# FdbkCtrl_v01.net
KiCad netlist of a schematic drawn in EAGLE
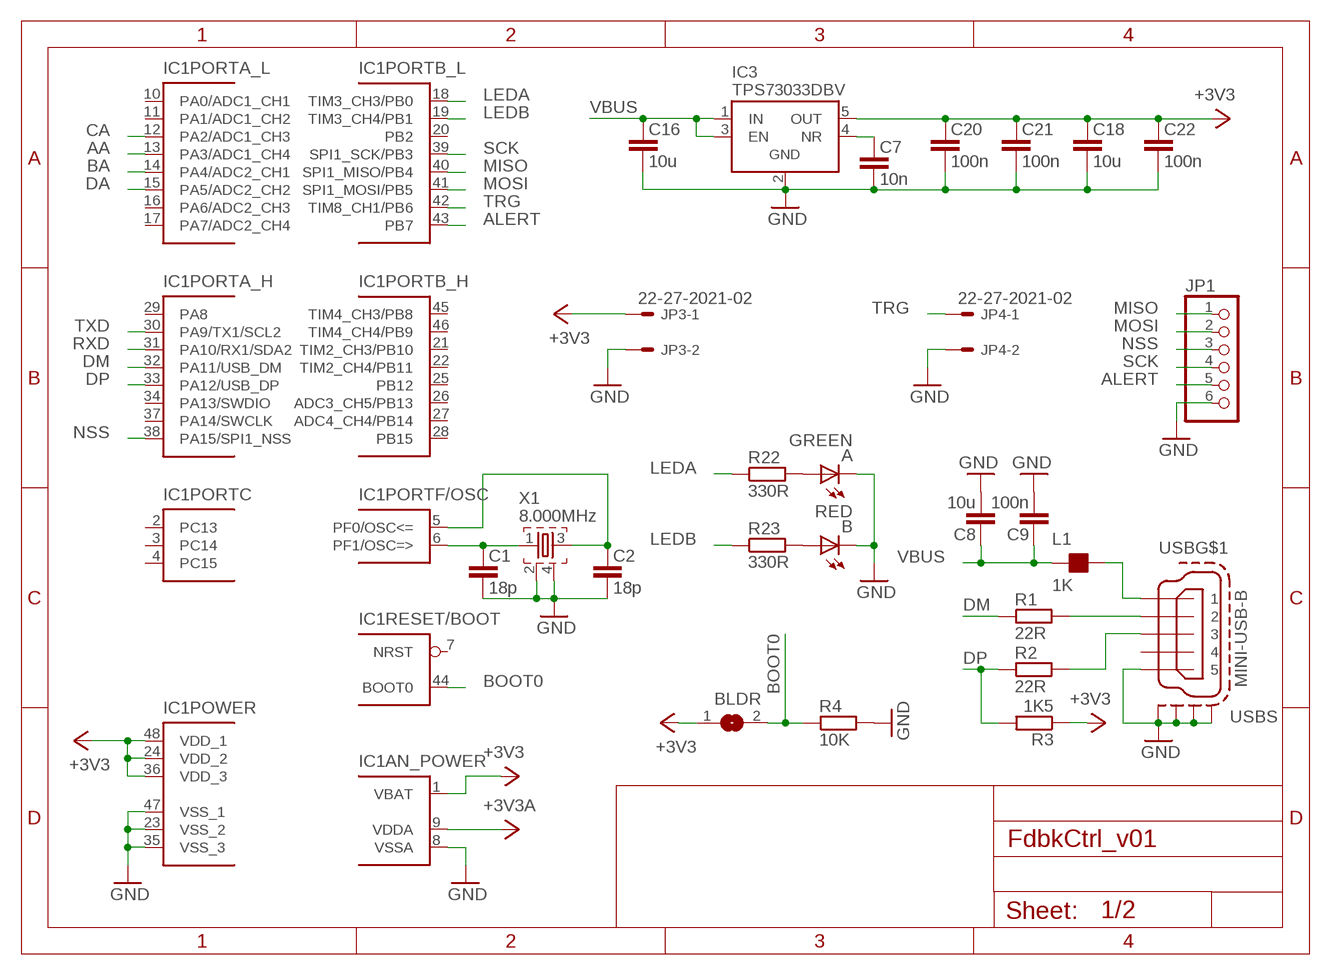
[diagram p0: schematic, sheet 1]
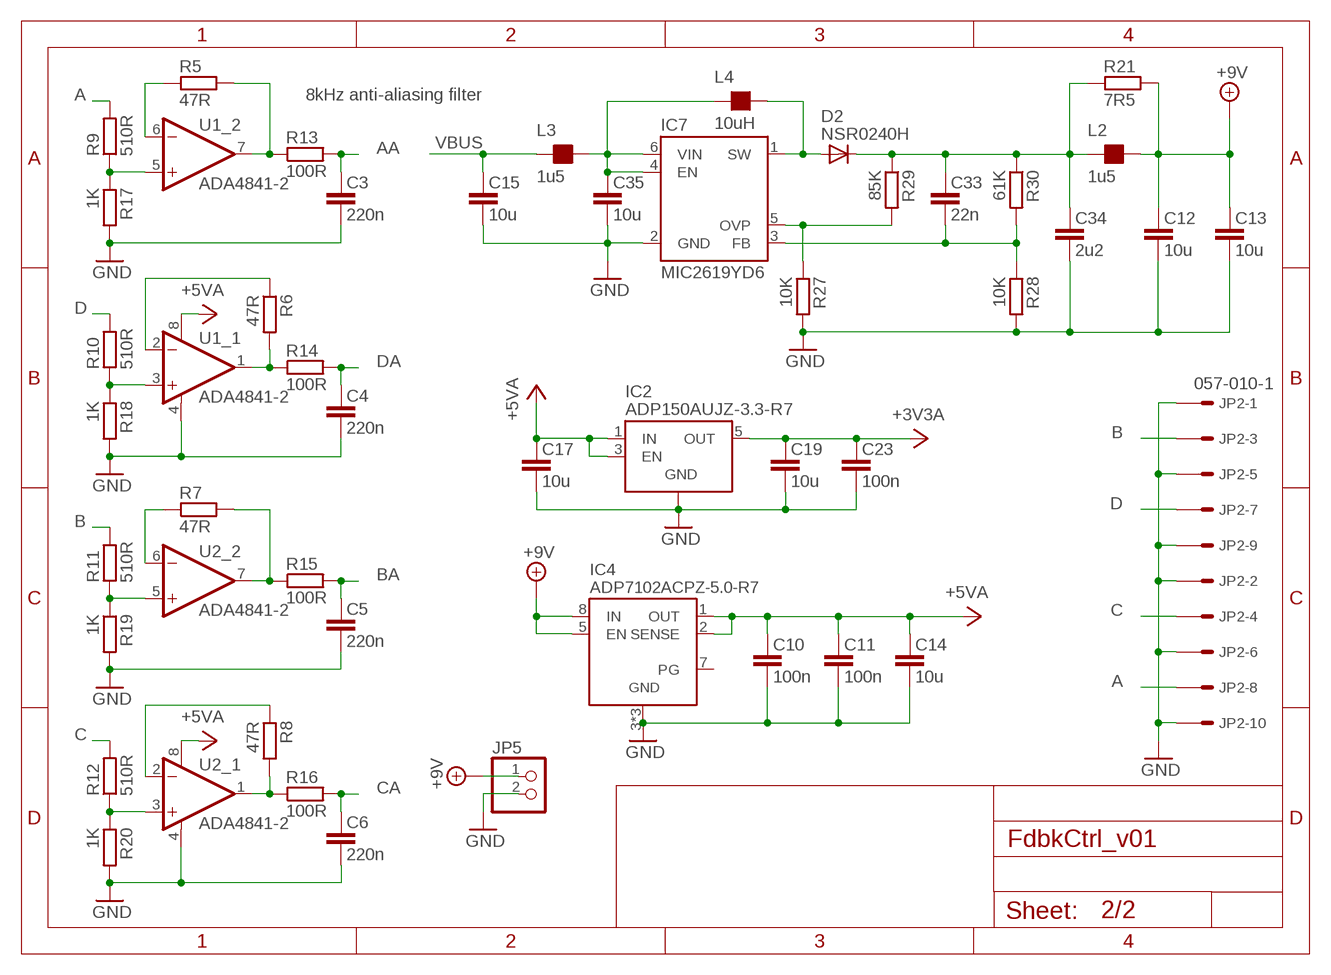
[diagram p1: schematic, sheet 2]

(export (version "E")
  (design (tool "Eeschema 10.0.6"))
  (components
    (comp (ref "C3")
      (value "220n")
      (footprint "eagle-import:C0603G")
      (libsource (lib "eagle-import") (part "C_EU_C0603G"))
    )
    (comp (ref "C4")
      (value "220n")
      (footprint "eagle-import:C0603G")
      (libsource (lib "eagle-import") (part "C_EU_C0603G"))
    )
    (comp (ref "C5")
      (value "220n")
      (footprint "eagle-import:C0603G")
      (libsource (lib "eagle-import") (part "C_EU_C0603G"))
    )
    (comp (ref "C6")
      (value "220n")
      (footprint "eagle-import:C0603G")
      (libsource (lib "eagle-import") (part "C_EU_C0603G"))
    )
    (comp (ref "C10")
      (value "100n")
      (footprint "eagle-import:C0603G")
      (libsource (lib "eagle-import") (part "C_EU_C0603G"))
    )
    (comp (ref "C11")
      (value "100n")
      (footprint "eagle-import:C0603G")
      (libsource (lib "eagle-import") (part "C_EU_C0603G"))
    )
    (comp (ref "C12")
      (value "10u")
      (footprint "eagle-import:C0805G")
      (libsource (lib "eagle-import") (part "C_EU_C0805G"))
    )
    (comp (ref "C13")
      (value "10u")
      (footprint "eagle-import:C0805G")
      (libsource (lib "eagle-import") (part "C_EU_C0805G"))
    )
    (comp (ref "C14")
      (value "10u")
      (footprint "eagle-import:C0805G")
      (libsource (lib "eagle-import") (part "C_EU_C0805G"))
    )
    (comp (ref "C15")
      (value "10u")
      (footprint "eagle-import:C0805G")
      (libsource (lib "eagle-import") (part "C_EU_C0805G"))
    )
    (comp (ref "C17")
      (value "10u")
      (footprint "eagle-import:C0805G")
      (libsource (lib "eagle-import") (part "C_EU_C0805G"))
    )
    (comp (ref "C19")
      (value "10u")
      (footprint "eagle-import:C0805G")
      (libsource (lib "eagle-import") (part "C_EU_C0805G"))
    )
    (comp (ref "C23")
      (value "100n")
      (footprint "eagle-import:C0402G")
      (libsource (lib "eagle-import") (part "C_EU_C0402G"))
    )
    (comp (ref "C33")
      (value "22n")
      (footprint "eagle-import:C0603")
      (libsource (lib "eagle-import") (part "C_EU_C0603"))
    )
    (comp (ref "C34")
      (value "2u2")
      (footprint "eagle-import:C0805G")
      (libsource (lib "eagle-import") (part "C_EU_C0805G"))
    )
    (comp (ref "C35")
      (value "10u")
      (footprint "eagle-import:C0805G")
      (libsource (lib "eagle-import") (part "C_EU_C0805G"))
    )
    (comp (ref "D2")
      (value "NSR0240H")
      (footprint "eagle-import:SOD323")
      (libsource (lib "eagle-import") (part "NSR0240H"))
    )
    (comp (ref "IC2")
      (value "ADP150AUJZ-3.3-R7")
      (footprint "eagle-import:SOT23-5")
      (libsource (lib "eagle-import") (part "ADP150AUJZ-3.3-R7"))
    )
    (comp (ref "IC4")
      (value "ADP7102ACPZ-5.0-R7")
      (footprint "eagle-import:LFCSP8")
      (libsource (lib "eagle-import") (part "ADP7102ACPZ-5.0-R7"))
    )
    (comp (ref "IC7")
      (value "MIC2619YD6")
      (footprint "eagle-import:SOT23-6")
      (libsource (lib "eagle-import") (part "MIC2619YD6"))
    )
    (comp (ref "JP2")
      (value "057-010-1")
      (footprint "eagle-import:057-010-1")
      (libsource (lib "eagle-import") (part "057-010-1"))
    )
    (comp (ref "JP5")
      (value "PINHD-1X2")
      (footprint "eagle-import:1X02")
      (libsource (lib "eagle-import") (part "PINHD-1X2"))
    )
    (comp (ref "L2")
      (value "1u5")
      (footprint "eagle-import:L2010")
      (libsource (lib "eagle-import") (part "FB_2010"))
    )
    (comp (ref "L3")
      (value "1u5")
      (footprint "eagle-import:L2010")
      (libsource (lib "eagle-import") (part "FB_2010"))
    )
    (comp (ref "L4")
      (value "10uH")
      (footprint "eagle-import:L1210")
      (libsource (lib "eagle-import") (part "FB_1210"))
    )
    (comp (ref "R5")
      (value "47R")
      (footprint "eagle-import:R0603")
      (libsource (lib "eagle-import") (part "R_EU_R0603"))
    )
    (comp (ref "R6")
      (value "47R")
      (footprint "eagle-import:R0603")
      (libsource (lib "eagle-import") (part "R_EU_R0603"))
    )
    (comp (ref "R7")
      (value "47R")
      (footprint "eagle-import:R0603")
      (libsource (lib "eagle-import") (part "R_EU_R0603"))
    )
    (comp (ref "R8")
      (value "47R")
      (footprint "eagle-import:R0603")
      (libsource (lib "eagle-import") (part "R_EU_R0603"))
    )
    (comp (ref "R9")
      (value "510R")
      (footprint "eagle-import:R0603")
      (libsource (lib "eagle-import") (part "R_EU_R0603"))
    )
    (comp (ref "R10")
      (value "510R")
      (footprint "eagle-import:R0603")
      (libsource (lib "eagle-import") (part "R_EU_R0603"))
    )
    (comp (ref "R11")
      (value "510R")
      (footprint "eagle-import:R0603")
      (libsource (lib "eagle-import") (part "R_EU_R0603"))
    )
    (comp (ref "R12")
      (value "510R")
      (footprint "eagle-import:R0603")
      (libsource (lib "eagle-import") (part "R_EU_R0603"))
    )
    (comp (ref "R13")
      (value "100R")
      (footprint "eagle-import:R0603")
      (libsource (lib "eagle-import") (part "R_EU_R0603"))
    )
    (comp (ref "R14")
      (value "100R")
      (footprint "eagle-import:R0603")
      (libsource (lib "eagle-import") (part "R_EU_R0603"))
    )
    (comp (ref "R15")
      (value "100R")
      (footprint "eagle-import:R0603")
      (libsource (lib "eagle-import") (part "R_EU_R0603"))
    )
    (comp (ref "R16")
      (value "100R")
      (footprint "eagle-import:R0603")
      (libsource (lib "eagle-import") (part "R_EU_R0603"))
    )
    (comp (ref "R17")
      (value "1K")
      (footprint "eagle-import:R0603G")
      (libsource (lib "eagle-import") (part "R_EU_R0603G"))
    )
    (comp (ref "R18")
      (value "1K")
      (footprint "eagle-import:R0603G")
      (libsource (lib "eagle-import") (part "R_EU_R0603G"))
    )
    (comp (ref "R19")
      (value "1K")
      (footprint "eagle-import:R0603G")
      (libsource (lib "eagle-import") (part "R_EU_R0603G"))
    )
    (comp (ref "R20")
      (value "1K")
      (footprint "eagle-import:R0603G")
      (libsource (lib "eagle-import") (part "R_EU_R0603G"))
    )
    (comp (ref "R21")
      (value "7R5")
      (footprint "eagle-import:R0805")
      (libsource (lib "eagle-import") (part "R_EU_R0805"))
    )
    (comp (ref "R27")
      (value "10K")
      (footprint "eagle-import:R0603G")
      (libsource (lib "eagle-import") (part "R_EU_R0603G"))
    )
    (comp (ref "R28")
      (value "10K")
      (footprint "eagle-import:R0603G")
      (libsource (lib "eagle-import") (part "R_EU_R0603G"))
    )
    (comp (ref "R29")
      (value "85K")
      (footprint "eagle-import:R0603")
      (libsource (lib "eagle-import") (part "R_EU_R0603"))
    )
    (comp (ref "R30")
      (value "61K")
      (footprint "eagle-import:R0603")
      (libsource (lib "eagle-import") (part "R_EU_R0603"))
    )
    (comp (ref "U1")
      (value "ADA4841-2")
      (footprint "eagle-import:SOIC-8")
      (libsource (lib "eagle-import") (part "ADA4841-2"))
    )
    (comp (ref "U2")
      (value "ADA4841-2")
      (footprint "eagle-import:SOIC-8")
      (libsource (lib "eagle-import") (part "ADA4841-2"))
    )
    (comp (ref "A")
      (value "GREEN")
      (footprint "eagle-import:CHIPLED_0805")
      (libsource (lib "eagle-import") (part "LEDCHIPLED_0805"))
    )
    (comp (ref "B")
      (value "RED")
      (footprint "eagle-import:CHIPLED_0805")
      (libsource (lib "eagle-import") (part "LEDCHIPLED_0805"))
    )
    (comp (ref "BLDR")
      (value "SJ")
      (footprint "eagle-import:SJ")
      (libsource (lib "eagle-import") (part "SJ"))
    )
    (comp (ref "C1")
      (value "18p")
      (footprint "eagle-import:C0603G")
      (libsource (lib "eagle-import") (part "C_EU_C0603G"))
    )
    (comp (ref "C2")
      (value "18p")
      (footprint "eagle-import:C0603G")
      (libsource (lib "eagle-import") (part "C_EU_C0603G"))
    )
    (comp (ref "C7")
      (value "10n")
      (footprint "eagle-import:C0402G")
      (libsource (lib "eagle-import") (part "C_EU_C0402G"))
    )
    (comp (ref "C8")
      (value "10u")
      (footprint "eagle-import:C0805G")
      (libsource (lib "eagle-import") (part "C_EU_C0805G"))
    )
    (comp (ref "C9")
      (value "100n")
      (footprint "eagle-import:C0603G")
      (libsource (lib "eagle-import") (part "C_EU_C0603G"))
    )
    (comp (ref "C16")
      (value "10u")
      (footprint "eagle-import:C0805G")
      (libsource (lib "eagle-import") (part "C_EU_C0805G"))
    )
    (comp (ref "C18")
      (value "10u")
      (footprint "eagle-import:C0805G")
      (libsource (lib "eagle-import") (part "C_EU_C0805G"))
    )
    (comp (ref "C20")
      (value "100n")
      (footprint "eagle-import:C0402G")
      (libsource (lib "eagle-import") (part "C_EU_C0402G"))
    )
    (comp (ref "C21")
      (value "100n")
      (footprint "eagle-import:C0402G")
      (libsource (lib "eagle-import") (part "C_EU_C0402G"))
    )
    (comp (ref "C22")
      (value "100n")
      (footprint "eagle-import:C0402G")
      (libsource (lib "eagle-import") (part "C_EU_C0402G"))
    )
    (comp (ref "IC1")
      (value "STM32F303CXT6")
      (footprint "eagle-import:LQFP48")
      (libsource (lib "eagle-import") (part "STM32F303CXT6"))
    )
    (comp (ref "IC3")
      (value "TPS73033DBV")
      (footprint "eagle-import:SOT23-5")
      (libsource (lib "eagle-import") (part "TPS73033DBV"))
    )
    (comp (ref "JP1")
      (value "PINHD-1X6")
      (footprint "eagle-import:1X06")
      (libsource (lib "eagle-import") (part "PINHD-1X6"))
    )
    (comp (ref "JP3")
      (value "22-27-2021-02")
      (footprint "eagle-import:6410-02")
      (libsource (lib "eagle-import") (part "22-?-0227-2021"))
    )
    (comp (ref "JP4")
      (value "22-27-2021-02")
      (footprint "eagle-import:6410-02")
      (libsource (lib "eagle-import") (part "22-?-0227-2021"))
    )
    (comp (ref "L1")
      (value "1K")
      (footprint "eagle-import:L0603")
      (libsource (lib "eagle-import") (part "FB_0603"))
    )
    (comp (ref "R1")
      (value "22R")
      (footprint "eagle-import:R0603")
      (libsource (lib "eagle-import") (part "R_EU_R0603"))
    )
    (comp (ref "R2")
      (value "22R")
      (footprint "eagle-import:R0603")
      (libsource (lib "eagle-import") (part "R_EU_R0603"))
    )
    (comp (ref "R3")
      (value "1K5")
      (footprint "eagle-import:R0603")
      (libsource (lib "eagle-import") (part "R_EU_R0603"))
    )
    (comp (ref "R4")
      (value "10K")
      (footprint "eagle-import:R0603G")
      (libsource (lib "eagle-import") (part "R_EU_R0603G"))
    )
    (comp (ref "R22")
      (value "330R")
      (footprint "eagle-import:R0603")
      (libsource (lib "eagle-import") (part "R_EU_R0603"))
    )
    (comp (ref "R23")
      (value "330R")
      (footprint "eagle-import:R0603")
      (libsource (lib "eagle-import") (part "R_EU_R0603"))
    )
    (comp (ref "USB")
      (value "MINI-USB-B")
      (footprint "eagle-import:32005-201")
      (libsource (lib "eagle-import") (part "MINI-USB-SCHIELD-32005-201"))
    )
    (comp (ref "X1")
      (value "8.000MHz")
      (footprint "eagle-import:ABMM2")
      (libsource (lib "eagle-import") (part "ABMM2"))
    )
  )
  (nets
    (net (code "1") (name "+3V3") (class "Default")
      (node (ref "BLDR") (pin "1") (pinfunction "1_1") (pintype "passive"))
      (node (ref "C18") (pin "1") (pinfunction "1_1") (pintype "passive"))
      (node (ref "C20") (pin "1") (pinfunction "1_1") (pintype "passive"))
      (node (ref "C21") (pin "1") (pinfunction "1_1") (pintype "passive"))
      (node (ref "C22") (pin "1") (pinfunction "1_1") (pintype "passive"))
      (node (ref "IC1") (pin "1") (pinfunction "VBAT_1") (pintype "power_in"))
      (node (ref "IC1") (pin "24") (pinfunction "VDD_2_24") (pintype "power_in"))
      (node (ref "IC1") (pin "36") (pinfunction "VDD_3_36") (pintype "power_in"))
      (node (ref "IC1") (pin "48") (pinfunction "VDD_1_48") (pintype "power_in"))
      (node (ref "IC3") (pin "5") (pinfunction "OUT_5") (pintype "power_in"))
      (node (ref "JP3") (pin "1") (pinfunction "S_1") (pintype "passive"))
      (node (ref "R3") (pin "1") (pinfunction "1_1") (pintype "passive"))
    )
    (net (code "2") (name "+3V3A") (class "Default")
      (node (ref "C19") (pin "1") (pinfunction "1_1") (pintype "passive"))
      (node (ref "C23") (pin "1") (pinfunction "1_1") (pintype "passive"))
      (node (ref "IC1") (pin "9") (pinfunction "VDDA_9") (pintype "power_in"))
      (node (ref "IC2") (pin "5") (pinfunction "OUT_5") (pintype "power_in"))
    )
    (net (code "3") (name "+5VA") (class "Default")
      (node (ref "C10") (pin "1") (pinfunction "1_1") (pintype "passive"))
      (node (ref "C11") (pin "1") (pinfunction "1_1") (pintype "passive"))
      (node (ref "C14") (pin "1") (pinfunction "1_1") (pintype "passive"))
      (node (ref "C17") (pin "1") (pinfunction "1_1") (pintype "passive"))
      (node (ref "IC2") (pin "1") (pinfunction "IN_1") (pintype "power_in"))
      (node (ref "IC2") (pin "3") (pinfunction "EN_3") (pintype "input"))
      (node (ref "IC4") (pin "1") (pinfunction "OUT_1") (pintype "power_in"))
      (node (ref "IC4") (pin "2") (pinfunction "SENSE_2") (pintype "input"))
      (node (ref "U1") (pin "8") (pinfunction "V+_8") (pintype "power_in"))
      (node (ref "U2") (pin "8") (pinfunction "V+_8") (pintype "power_in"))
    )
    (net (code "4") (name "+9V") (class "Default")
      (node (ref "C12") (pin "1") (pinfunction "1_1") (pintype "passive"))
      (node (ref "C13") (pin "1") (pinfunction "1_1") (pintype "passive"))
      (node (ref "IC4") (pin "5") (pinfunction "EN_5") (pintype "input"))
      (node (ref "IC4") (pin "8") (pinfunction "IN_8") (pintype "power_in"))
      (node (ref "JP5") (pin "1") (pinfunction "1_1") (pintype "passive"))
      (node (ref "L2") (pin "2") (pinfunction "2_2") (pintype "passive"))
      (node (ref "R21") (pin "2") (pinfunction "2_2") (pintype "passive"))
    )
    (net (code "5") (name "A") (class "Default")
      (node (ref "JP2") (pin "8") (pinfunction "S_8") (pintype "passive"))
      (node (ref "R9") (pin "2") (pinfunction "2_2") (pintype "passive"))
    )
    (net (code "6") (name "AA") (class "Default")
      (node (ref "C3") (pin "1") (pinfunction "1_1") (pintype "passive"))
      (node (ref "IC1") (pin "13") (pinfunction "PA3/ADC1_CH4_13") (pintype "bidirectional"))
      (node (ref "R13") (pin "2") (pinfunction "2_2") (pintype "passive"))
    )
    (net (code "7") (name "ALERT") (class "Default")
      (node (ref "IC1") (pin "43") (pinfunction "PB7_43") (pintype "bidirectional"))
      (node (ref "JP1") (pin "5") (pinfunction "5_5") (pintype "passive"))
    )
    (net (code "8") (name "B") (class "Default")
      (node (ref "JP2") (pin "3") (pinfunction "S_3") (pintype "passive"))
      (node (ref "R11") (pin "2") (pinfunction "2_2") (pintype "passive"))
    )
    (net (code "9") (name "BA") (class "Default")
      (node (ref "C5") (pin "1") (pinfunction "1_1") (pintype "passive"))
      (node (ref "IC1") (pin "14") (pinfunction "PA4/ADC2_CH1_14") (pintype "bidirectional"))
      (node (ref "R15") (pin "2") (pinfunction "2_2") (pintype "passive"))
    )
    (net (code "10") (name "BOOT0") (class "Default")
      (node (ref "BLDR") (pin "2") (pinfunction "2_2") (pintype "passive"))
      (node (ref "IC1") (pin "44") (pinfunction "BOOT0_44") (pintype "input"))
      (node (ref "R4") (pin "1") (pinfunction "1_1") (pintype "passive"))
    )
    (net (code "11") (name "C") (class "Default")
      (node (ref "JP2") (pin "4") (pinfunction "S_4") (pintype "passive"))
      (node (ref "R12") (pin "2") (pinfunction "2_2") (pintype "passive"))
    )
    (net (code "12") (name "CA") (class "Default")
      (node (ref "C6") (pin "1") (pinfunction "1_1") (pintype "passive"))
      (node (ref "IC1") (pin "12") (pinfunction "PA2/ADC1_CH3_12") (pintype "bidirectional"))
      (node (ref "R16") (pin "2") (pinfunction "2_2") (pintype "passive"))
    )
    (net (code "13") (name "D") (class "Default")
      (node (ref "JP2") (pin "7") (pinfunction "S_7") (pintype "passive"))
      (node (ref "R10") (pin "2") (pinfunction "2_2") (pintype "passive"))
    )
    (net (code "14") (name "DA") (class "Default")
      (node (ref "C4") (pin "1") (pinfunction "1_1") (pintype "passive"))
      (node (ref "IC1") (pin "15") (pinfunction "PA5/ADC2_CH2_15") (pintype "bidirectional"))
      (node (ref "R14") (pin "2") (pinfunction "2_2") (pintype "passive"))
    )
    (net (code "15") (name "DM") (class "Default")
      (node (ref "IC1") (pin "32") (pinfunction "PA11/USB_DM_32") (pintype "bidirectional"))
      (node (ref "R1") (pin "1") (pinfunction "1_1") (pintype "passive"))
    )
    (net (code "16") (name "DP") (class "Default")
      (node (ref "IC1") (pin "33") (pinfunction "PA12/USB_DP_33") (pintype "bidirectional"))
      (node (ref "R2") (pin "1") (pinfunction "1_1") (pintype "passive"))
      (node (ref "R3") (pin "2") (pinfunction "2_2") (pintype "passive"))
    )
    (net (code "17") (name "GND") (class "Default")
      (node (ref "A") (pin "C") (pinfunction "C_C") (pintype "passive"))
      (node (ref "B") (pin "C") (pinfunction "C_C") (pintype "passive"))
      (node (ref "C1") (pin "2") (pinfunction "2_2") (pintype "passive"))
      (node (ref "C10") (pin "2") (pinfunction "2_2") (pintype "passive"))
      (node (ref "C11") (pin "2") (pinfunction "2_2") (pintype "passive"))
      (node (ref "C12") (pin "2") (pinfunction "2_2") (pintype "passive"))
      (node (ref "C13") (pin "2") (pinfunction "2_2") (pintype "passive"))
      (node (ref "C14") (pin "2") (pinfunction "2_2") (pintype "passive"))
      (node (ref "C15") (pin "2") (pinfunction "2_2") (pintype "passive"))
      (node (ref "C16") (pin "2") (pinfunction "2_2") (pintype "passive"))
      (node (ref "C17") (pin "2") (pinfunction "2_2") (pintype "passive"))
      (node (ref "C18") (pin "2") (pinfunction "2_2") (pintype "passive"))
      (node (ref "C19") (pin "2") (pinfunction "2_2") (pintype "passive"))
      (node (ref "C2") (pin "2") (pinfunction "2_2") (pintype "passive"))
      (node (ref "C20") (pin "2") (pinfunction "2_2") (pintype "passive"))
      (node (ref "C21") (pin "2") (pinfunction "2_2") (pintype "passive"))
      (node (ref "C22") (pin "2") (pinfunction "2_2") (pintype "passive"))
      (node (ref "C23") (pin "2") (pinfunction "2_2") (pintype "passive"))
      (node (ref "C3") (pin "2") (pinfunction "2_2") (pintype "passive"))
      (node (ref "C34") (pin "2") (pinfunction "2_2") (pintype "passive"))
      (node (ref "C35") (pin "2") (pinfunction "2_2") (pintype "passive"))
      (node (ref "C4") (pin "2") (pinfunction "2_2") (pintype "passive"))
      (node (ref "C5") (pin "2") (pinfunction "2_2") (pintype "passive"))
      (node (ref "C6") (pin "2") (pinfunction "2_2") (pintype "passive"))
      (node (ref "C7") (pin "2") (pinfunction "2_2") (pintype "passive"))
      (node (ref "C8") (pin "2") (pinfunction "2_2") (pintype "passive"))
      (node (ref "C9") (pin "2") (pinfunction "2_2") (pintype "passive"))
      (node (ref "IC1") (pin "23") (pinfunction "VSS_2_23") (pintype "power_in"))
      (node (ref "IC1") (pin "35") (pinfunction "VSS_3_35") (pintype "power_in"))
      (node (ref "IC1") (pin "47") (pinfunction "VSS_1_47") (pintype "power_in"))
      (node (ref "IC1") (pin "8") (pinfunction "VSSA_8") (pintype "power_in"))
      (node (ref "IC2") (pin "2") (pinfunction "GND_2") (pintype "power_in"))
      (node (ref "IC3") (pin "2") (pinfunction "GND_2") (pintype "power_in"))
      (node (ref "IC4") (pin "3") (pinfunction "GND_3") (pintype "power_in"))
      (node (ref "IC4") (pin "6") (pinfunction "GND_6") (pintype "power_in"))
      (node (ref "IC4") (pin "EP") (pinfunction "GND_EP") (pintype "power_in"))
      (node (ref "IC7") (pin "2") (pinfunction "GND_2") (pintype "power_in"))
      (node (ref "JP1") (pin "6") (pinfunction "6_6") (pintype "passive"))
      (node (ref "JP2") (pin "1") (pinfunction "S_1") (pintype "passive"))
      (node (ref "JP2") (pin "10") (pinfunction "S_10") (pintype "passive"))
      (node (ref "JP2") (pin "2") (pinfunction "S_2") (pintype "passive"))
      (node (ref "JP2") (pin "5") (pinfunction "S_5") (pintype "passive"))
      (node (ref "JP2") (pin "6") (pinfunction "S_6") (pintype "passive"))
      (node (ref "JP2") (pin "9") (pinfunction "S_9") (pintype "passive"))
      (node (ref "JP3") (pin "2") (pinfunction "S_2") (pintype "passive"))
      (node (ref "JP4") (pin "2") (pinfunction "S_2") (pintype "passive"))
      (node (ref "JP5") (pin "2") (pinfunction "2_2") (pintype "passive"))
      (node (ref "R17") (pin "2") (pinfunction "2_2") (pintype "passive"))
      (node (ref "R18") (pin "2") (pinfunction "2_2") (pintype "passive"))
      (node (ref "R19") (pin "2") (pinfunction "2_2") (pintype "passive"))
      (node (ref "R20") (pin "2") (pinfunction "2_2") (pintype "passive"))
      (node (ref "R27") (pin "2") (pinfunction "2_2") (pintype "passive"))
      (node (ref "R28") (pin "2") (pinfunction "2_2") (pintype "passive"))
      (node (ref "R4") (pin "2") (pinfunction "2_2") (pintype "passive"))
      (node (ref "U1") (pin "4") (pinfunction "V-_4") (pintype "power_in"))
      (node (ref "U2") (pin "4") (pinfunction "V-_4") (pintype "power_in"))
      (node (ref "USB") (pin "5") (pinfunction "5_5") (pintype "passive"))
      (node (ref "USB") (pin "M1") (pinfunction "S1_M1") (pintype "passive"))
      (node (ref "USB") (pin "M2") (pinfunction "S2_M2") (pintype "passive"))
      (node (ref "USB") (pin "M3") (pinfunction "S3_M3") (pintype "passive"))
      (node (ref "USB") (pin "M4") (pinfunction "S4_M4") (pintype "passive"))
      (node (ref "X1") (pin "2") (pinfunction "2_2") (pintype "passive"))
      (node (ref "X1") (pin "4") (pinfunction "4_4") (pintype "passive"))
    )
    (net (code "18") (name "LEDA") (class "Default")
      (node (ref "IC1") (pin "18") (pinfunction "TIM3_CH3/PB0_18") (pintype "bidirectional"))
      (node (ref "R22") (pin "1") (pinfunction "1_1") (pintype "passive"))
    )
    (net (code "19") (name "LEDB") (class "Default")
      (node (ref "IC1") (pin "19") (pinfunction "TIM3_CH4/PB1_19") (pintype "bidirectional"))
      (node (ref "R23") (pin "1") (pinfunction "1_1") (pintype "passive"))
    )
    (net (code "20") (name "MISO") (class "Default")
      (node (ref "IC1") (pin "40") (pinfunction "SPI1_MISO/PB4_40") (pintype "bidirectional"))
      (node (ref "JP1") (pin "1") (pinfunction "1_1") (pintype "passive"))
    )
    (net (code "21") (name "MOSI") (class "Default")
      (node (ref "IC1") (pin "41") (pinfunction "SPI1_MOSI/PB5_41") (pintype "bidirectional"))
      (node (ref "JP1") (pin "2") (pinfunction "2_2") (pintype "passive"))
    )
    (net (code "22") (name "NSS") (class "Default")
      (node (ref "IC1") (pin "38") (pinfunction "PA15/SPI1_NSS_38") (pintype "bidirectional"))
      (node (ref "JP1") (pin "3") (pinfunction "3_3") (pintype "passive"))
    )
    (net (code "23") (name "Net-(A-PadA)") (class "Default")
      (node (ref "A") (pin "A") (pinfunction "A_A") (pintype "passive"))
      (node (ref "R22") (pin "2") (pinfunction "2_2") (pintype "passive"))
    )
    (net (code "24") (name "Net-(B-PadA)") (class "Default")
      (node (ref "B") (pin "A") (pinfunction "A_A") (pintype "passive"))
      (node (ref "R23") (pin "2") (pinfunction "2_2") (pintype "passive"))
    )
    (net (code "25") (name "Net-(C33-Pad1)") (class "Default")
      (node (ref "C33") (pin "1") (pinfunction "1_1") (pintype "passive"))
      (node (ref "C34") (pin "1") (pinfunction "1_1") (pintype "passive"))
      (node (ref "D2") (pin "C") (pinfunction "C_C") (pintype "passive"))
      (node (ref "L2") (pin "1") (pinfunction "1_1") (pintype "passive"))
      (node (ref "R21") (pin "1") (pinfunction "1_1") (pintype "passive"))
      (node (ref "R29") (pin "1") (pinfunction "1_1") (pintype "passive"))
      (node (ref "R30") (pin "1") (pinfunction "1_1") (pintype "passive"))
    )
    (net (code "26") (name "Net-(IC1G-PF0{slash}OSC<=)") (class "Default")
      (node (ref "C2") (pin "1") (pinfunction "1_1") (pintype "passive"))
      (node (ref "IC1") (pin "5") (pinfunction "PF0/OSC<=_5") (pintype "bidirectional"))
      (node (ref "X1") (pin "3") (pinfunction "3_3") (pintype "passive"))
    )
    (net (code "27") (name "Net-(IC1G-PF1{slash}OSC=>)") (class "Default")
      (node (ref "C1") (pin "1") (pinfunction "1_1") (pintype "passive"))
      (node (ref "IC1") (pin "6") (pinfunction "PF1/OSC=>_6") (pintype "bidirectional"))
      (node (ref "X1") (pin "1") (pinfunction "1_1") (pintype "passive"))
    )
    (net (code "28") (name "Net-(IC3-NR)") (class "Default")
      (node (ref "C7") (pin "1") (pinfunction "1_1") (pintype "passive"))
      (node (ref "IC3") (pin "4") (pinfunction "NR_4") (pintype "passive"))
    )
    (net (code "29") (name "Net-(IC7-EN)") (class "Default")
      (node (ref "C35") (pin "1") (pinfunction "1_1") (pintype "passive"))
      (node (ref "IC7") (pin "4") (pinfunction "EN_4") (pintype "input"))
      (node (ref "IC7") (pin "6") (pinfunction "VIN_6") (pintype "power_in"))
      (node (ref "L3") (pin "2") (pinfunction "2_2") (pintype "passive"))
      (node (ref "L4") (pin "1") (pinfunction "1_1") (pintype "passive"))
    )
    (net (code "30") (name "Net-(IC7-FB)") (class "Default")
      (node (ref "C33") (pin "2") (pinfunction "2_2") (pintype "passive"))
      (node (ref "IC7") (pin "3") (pinfunction "FB_3") (pintype "input"))
      (node (ref "R28") (pin "1") (pinfunction "1_1") (pintype "passive"))
      (node (ref "R30") (pin "2") (pinfunction "2_2") (pintype "passive"))
    )
    (net (code "31") (name "Net-(IC7-OVP)") (class "Default")
      (node (ref "IC7") (pin "5") (pinfunction "OVP_5") (pintype "input"))
      (node (ref "R27") (pin "1") (pinfunction "1_1") (pintype "passive"))
      (node (ref "R29") (pin "2") (pinfunction "2_2") (pintype "passive"))
    )
    (net (code "32") (name "Net-(IC7-SW)") (class "Default")
      (node (ref "D2") (pin "A") (pinfunction "A_A") (pintype "passive"))
      (node (ref "IC7") (pin "1") (pinfunction "SW_1") (pintype "input"))
      (node (ref "L4") (pin "2") (pinfunction "2_2") (pintype "passive"))
    )
    (net (code "33") (name "Net-(L1-Pad2)") (class "Default")
      (node (ref "L1") (pin "2") (pinfunction "2_2") (pintype "passive"))
      (node (ref "USB") (pin "1") (pinfunction "1_1") (pintype "passive"))
    )
    (net (code "34") (name "Net-(R1-Pad2)") (class "Default")
      (node (ref "R1") (pin "2") (pinfunction "2_2") (pintype "passive"))
      (node (ref "USB") (pin "2") (pinfunction "2_2") (pintype "passive"))
    )
    (net (code "35") (name "Net-(R2-Pad2)") (class "Default")
      (node (ref "R2") (pin "2") (pinfunction "2_2") (pintype "passive"))
      (node (ref "USB") (pin "3") (pinfunction "3_3") (pintype "passive"))
    )
    (net (code "36") (name "Net-(U1A-+IN)") (class "Default")
      (node (ref "R10") (pin "1") (pinfunction "1_1") (pintype "passive"))
      (node (ref "R18") (pin "1") (pinfunction "1_1") (pintype "passive"))
      (node (ref "U1") (pin "3") (pinfunction "+IN_3") (pintype "input"))
    )
    (net (code "37") (name "Net-(U1A--IN)") (class "Default")
      (node (ref "R6") (pin "1") (pinfunction "1_1") (pintype "passive"))
      (node (ref "U1") (pin "2") (pinfunction "-IN_2") (pintype "input"))
    )
    (net (code "38") (name "Net-(U1A-OUT)") (class "Default")
      (node (ref "R14") (pin "1") (pinfunction "1_1") (pintype "passive"))
      (node (ref "R6") (pin "2") (pinfunction "2_2") (pintype "passive"))
      (node (ref "U1") (pin "1") (pinfunction "OUT_1") (pintype "output"))
    )
    (net (code "39") (name "Net-(U1B-+IN)") (class "Default")
      (node (ref "R17") (pin "1") (pinfunction "1_1") (pintype "passive"))
      (node (ref "R9") (pin "1") (pinfunction "1_1") (pintype "passive"))
      (node (ref "U1") (pin "5") (pinfunction "+IN_5") (pintype "input"))
    )
    (net (code "40") (name "Net-(U1B--IN)") (class "Default")
      (node (ref "R5") (pin "1") (pinfunction "1_1") (pintype "passive"))
      (node (ref "U1") (pin "6") (pinfunction "-IN_6") (pintype "input"))
    )
    (net (code "41") (name "Net-(U1B-OUT)") (class "Default")
      (node (ref "R13") (pin "1") (pinfunction "1_1") (pintype "passive"))
      (node (ref "R5") (pin "2") (pinfunction "2_2") (pintype "passive"))
      (node (ref "U1") (pin "7") (pinfunction "OUT_7") (pintype "output"))
    )
    (net (code "42") (name "Net-(U2A-+IN)") (class "Default")
      (node (ref "R12") (pin "1") (pinfunction "1_1") (pintype "passive"))
      (node (ref "R20") (pin "1") (pinfunction "1_1") (pintype "passive"))
      (node (ref "U2") (pin "3") (pinfunction "+IN_3") (pintype "input"))
    )
    (net (code "43") (name "Net-(U2A--IN)") (class "Default")
      (node (ref "R8") (pin "1") (pinfunction "1_1") (pintype "passive"))
      (node (ref "U2") (pin "2") (pinfunction "-IN_2") (pintype "input"))
    )
    (net (code "44") (name "Net-(U2A-OUT)") (class "Default")
      (node (ref "R16") (pin "1") (pinfunction "1_1") (pintype "passive"))
      (node (ref "R8") (pin "2") (pinfunction "2_2") (pintype "passive"))
      (node (ref "U2") (pin "1") (pinfunction "OUT_1") (pintype "output"))
    )
    (net (code "45") (name "Net-(U2B-+IN)") (class "Default")
      (node (ref "R11") (pin "1") (pinfunction "1_1") (pintype "passive"))
      (node (ref "R19") (pin "1") (pinfunction "1_1") (pintype "passive"))
      (node (ref "U2") (pin "5") (pinfunction "+IN_5") (pintype "input"))
    )
    (net (code "46") (name "Net-(U2B--IN)") (class "Default")
      (node (ref "R7") (pin "1") (pinfunction "1_1") (pintype "passive"))
      (node (ref "U2") (pin "6") (pinfunction "-IN_6") (pintype "input"))
    )
    (net (code "47") (name "Net-(U2B-OUT)") (class "Default")
      (node (ref "R15") (pin "1") (pinfunction "1_1") (pintype "passive"))
      (node (ref "R7") (pin "2") (pinfunction "2_2") (pintype "passive"))
      (node (ref "U2") (pin "7") (pinfunction "OUT_7") (pintype "output"))
    )
    (net (code "48") (name "RXD") (class "Default")
      (node (ref "IC1") (pin "31") (pinfunction "PA10/RX1/SDA2_31") (pintype "bidirectional"))
    )
    (net (code "49") (name "SCK") (class "Default")
      (node (ref "IC1") (pin "39") (pinfunction "SPI1_SCK/PB3_39") (pintype "bidirectional"))
      (node (ref "JP1") (pin "4") (pinfunction "4_4") (pintype "passive"))
    )
    (net (code "50") (name "TRG") (class "Default")
      (node (ref "IC1") (pin "42") (pinfunction "TIM8_CH1/PB6_42") (pintype "bidirectional"))
      (node (ref "JP4") (pin "1") (pinfunction "S_1") (pintype "passive"))
    )
    (net (code "51") (name "TXD") (class "Default")
      (node (ref "IC1") (pin "30") (pinfunction "PA9/TX1/SCL2_30") (pintype "bidirectional"))
    )
    (net (code "52") (name "VBUS") (class "Default")
      (node (ref "C15") (pin "1") (pinfunction "1_1") (pintype "passive"))
      (node (ref "C16") (pin "1") (pinfunction "1_1") (pintype "passive"))
      (node (ref "C8") (pin "1") (pinfunction "1_1") (pintype "passive"))
      (node (ref "C9") (pin "1") (pinfunction "1_1") (pintype "passive"))
      (node (ref "IC3") (pin "1") (pinfunction "IN_1") (pintype "power_in"))
      (node (ref "IC3") (pin "3") (pinfunction "EN_3") (pintype "input"))
      (node (ref "L1") (pin "1") (pinfunction "1_1") (pintype "passive"))
      (node (ref "L3") (pin "1") (pinfunction "1_1") (pintype "passive"))
    )
    (net (code "53") (name "unconnected-(IC1B-PA8-Pad29)") (class "Default")
      (node (ref "IC1") (pin "29") (pinfunction "PA8_29") (pintype "bidirectional"))
    )
    (net (code "54") (name "unconnected-(IC1B-PA13{slash}SWDIO-Pad34)") (class "Default")
      (node (ref "IC1") (pin "34") (pinfunction "PA13/SWDIO_34") (pintype "bidirectional"))
    )
    (net (code "55") (name "unconnected-(IC1B-PA14{slash}SWCLK-Pad37)") (class "Default")
      (node (ref "IC1") (pin "37") (pinfunction "PA14/SWCLK_37") (pintype "bidirectional"))
    )
    (net (code "56") (name "unconnected-(IC1C-PA0{slash}ADC1_CH1-Pad10)") (class "Default")
      (node (ref "IC1") (pin "10") (pinfunction "PA0/ADC1_CH1_10") (pintype "bidirectional"))
    )
    (net (code "57") (name "unconnected-(IC1C-PA1{slash}ADC1_CH2-Pad11)") (class "Default")
      (node (ref "IC1") (pin "11") (pinfunction "PA1/ADC1_CH2_11") (pintype "bidirectional"))
    )
    (net (code "58") (name "unconnected-(IC1C-PA6{slash}ADC2_CH3-Pad16)") (class "Default")
      (node (ref "IC1") (pin "16") (pinfunction "PA6/ADC2_CH3_16") (pintype "bidirectional"))
    )
    (net (code "59") (name "unconnected-(IC1C-PA7{slash}ADC2_CH4-Pad17)") (class "Default")
      (node (ref "IC1") (pin "17") (pinfunction "PA7/ADC2_CH4_17") (pintype "bidirectional"))
    )
    (net (code "60") (name "unconnected-(IC1D-ADC3_CH5{slash}PB13-Pad26)") (class "Default")
      (node (ref "IC1") (pin "26") (pinfunction "ADC3_CH5/PB13_26") (pintype "bidirectional"))
    )
    (net (code "61") (name "unconnected-(IC1D-ADC4_CH4{slash}PB14-Pad27)") (class "Default")
      (node (ref "IC1") (pin "27") (pinfunction "ADC4_CH4/PB14_27") (pintype "bidirectional"))
    )
    (net (code "62") (name "unconnected-(IC1D-PB12-Pad25)") (class "Default")
      (node (ref "IC1") (pin "25") (pinfunction "PB12_25") (pintype "bidirectional"))
    )
    (net (code "63") (name "unconnected-(IC1D-PB15-Pad28)") (class "Default")
      (node (ref "IC1") (pin "28") (pinfunction "PB15_28") (pintype "bidirectional"))
    )
    (net (code "64") (name "unconnected-(IC1D-TIM2_CH3{slash}PB10-Pad21)") (class "Default")
      (node (ref "IC1") (pin "21") (pinfunction "TIM2_CH3/PB10_21") (pintype "bidirectional"))
    )
    (net (code "65") (name "unconnected-(IC1D-TIM2_CH4{slash}PB11-Pad22)") (class "Default")
      (node (ref "IC1") (pin "22") (pinfunction "TIM2_CH4/PB11_22") (pintype "bidirectional"))
    )
    (net (code "66") (name "unconnected-(IC1D-TIM4_CH3{slash}PB8-Pad45)") (class "Default")
      (node (ref "IC1") (pin "45") (pinfunction "TIM4_CH3/PB8_45") (pintype "bidirectional"))
    )
    (net (code "67") (name "unconnected-(IC1D-TIM4_CH4{slash}PB9-Pad46)") (class "Default")
      (node (ref "IC1") (pin "46") (pinfunction "TIM4_CH4/PB9_46") (pintype "bidirectional"))
    )
    (net (code "68") (name "unconnected-(IC1E-PB2-Pad20)") (class "Default")
      (node (ref "IC1") (pin "20") (pinfunction "PB2_20") (pintype "bidirectional"))
    )
    (net (code "69") (name "unconnected-(IC1F-PC13-Pad2)") (class "Default")
      (node (ref "IC1") (pin "2") (pinfunction "PC13_2") (pintype "bidirectional"))
    )
    (net (code "70") (name "unconnected-(IC1F-PC14-Pad3)") (class "Default")
      (node (ref "IC1") (pin "3") (pinfunction "PC14_3") (pintype "bidirectional"))
    )
    (net (code "71") (name "unconnected-(IC1F-PC15-Pad4)") (class "Default")
      (node (ref "IC1") (pin "4") (pinfunction "PC15_4") (pintype "bidirectional"))
    )
    (net (code "72") (name "unconnected-(IC1I-NRST-Pad7)") (class "Default")
      (node (ref "IC1") (pin "7") (pinfunction "NRST_7") (pintype "input"))
    )
    (net (code "73") (name "unconnected-(IC4-PG-Pad7)") (class "Default")
      (node (ref "IC4") (pin "7") (pinfunction "PG_7") (pintype "open_collector"))
    )
    (net (code "74") (name "unconnected-(USB-Pad4)") (class "Default")
      (node (ref "USB") (pin "4") (pinfunction "4_4") (pintype "passive"))
    )
  )
)
